# Distance-Alarm.net
KiCad netlist of a schematic drawn in EAGLE
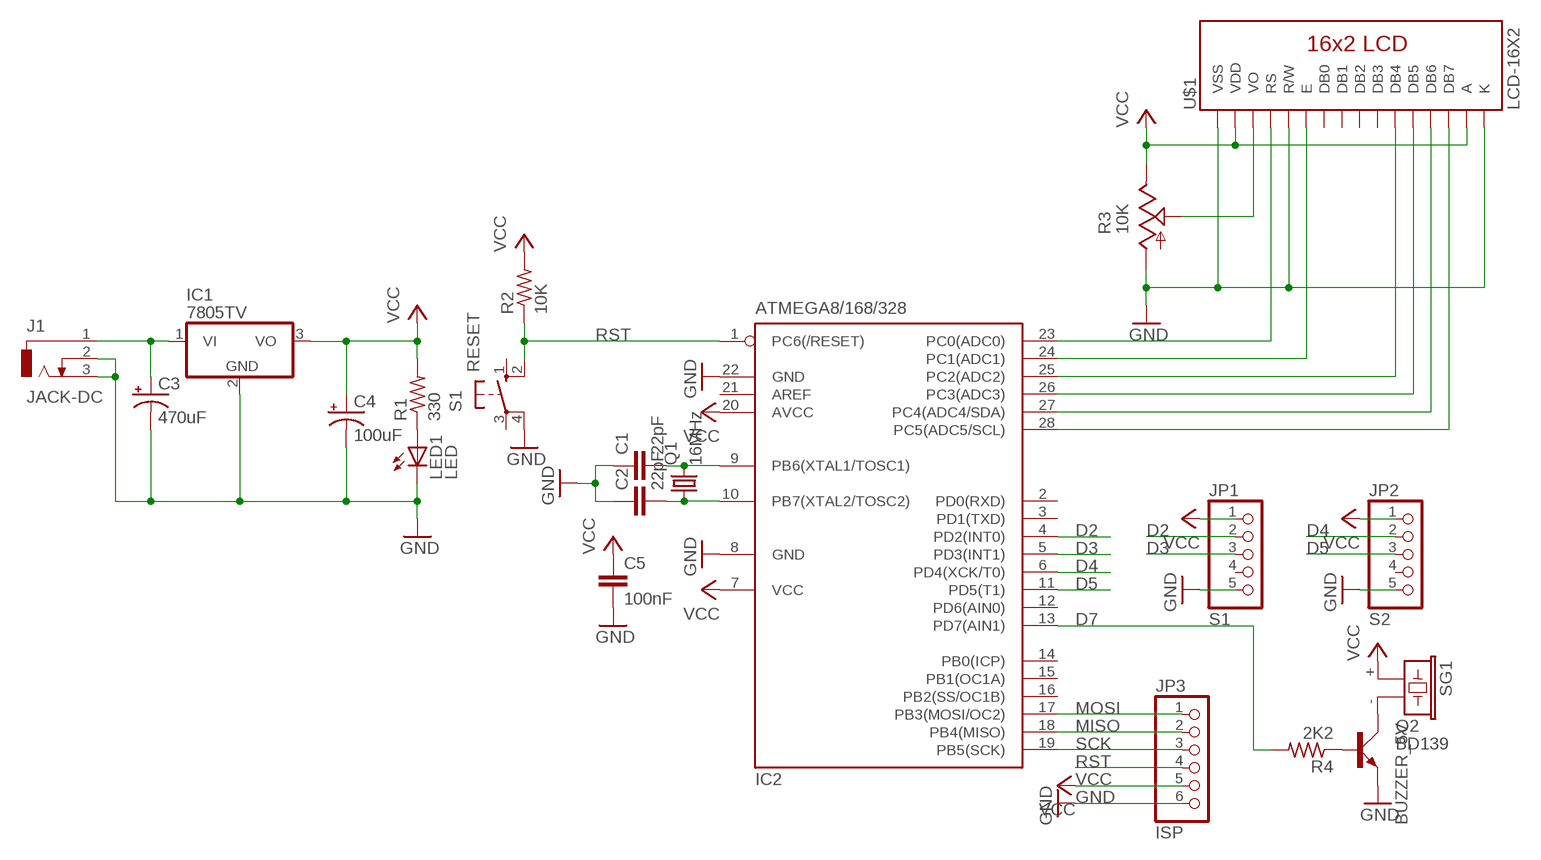
[diagram p0: schematic, sheet 1]

(export (version "E")
  (design (tool "Eeschema 10.0.6"))
  (components
    (comp (ref "C1")
      (value "22pF")
      (footprint "eagle-import:C025-024X044")
      (libsource (lib "eagle-import") (part "CAPACITOR-NONPOLAR025-024X044"))
    )
    (comp (ref "C2")
      (value "22pF")
      (footprint "eagle-import:C025-024X044")
      (libsource (lib "eagle-import") (part "CAPACITOR-NONPOLAR025-024X044"))
    )
    (comp (ref "C3")
      (value "470uF")
      (footprint "eagle-import:E2,5-6")
      (libsource (lib "eagle-import") (part "CAPACITOR-POLARE2.5-6"))
    )
    (comp (ref "C4")
      (value "100uF")
      (footprint "eagle-import:E2,5-6")
      (libsource (lib "eagle-import") (part "CAPACITOR-POLARE2.5-6"))
    )
    (comp (ref "C5")
      (value "100nF")
      (footprint "eagle-import:C025-024X044")
      (libsource (lib "eagle-import") (part "CAPACITOR-NONPOLAR025-024X044"))
    )
    (comp (ref "IC1")
      (value "7805TV")
      (footprint "eagle-import:TO220V")
      (libsource (lib "eagle-import") (part "78TV05"))
    )
    (comp (ref "IC2")
      (value "ATMEGA8/168/328")
      (footprint "eagle-import:DIL28-3")
      (libsource (lib "eagle-import") (part "ATMEGA8/168/328"))
    )
    (comp (ref "J1")
      (value "JACK-DC")
      (footprint "eagle-import:DCJ0202")
      (libsource (lib "eagle-import") (part "JACK-DC"))
    )
    (comp (ref "JP1")
      (value "S1")
      (footprint "eagle-import:1X05")
      (libsource (lib "eagle-import") (part "PINHD-1X5"))
    )
    (comp (ref "JP2")
      (value "S2")
      (footprint "eagle-import:1X05")
      (libsource (lib "eagle-import") (part "PINHD-1X5"))
    )
    (comp (ref "JP3")
      (value "ISP")
      (footprint "eagle-import:1X06")
      (libsource (lib "eagle-import") (part "PINHD-1X6"))
    )
    (comp (ref "LED1")
      (value "LED")
      (footprint "eagle-import:LED3MM")
      (libsource (lib "eagle-import") (part "LED3MM"))
    )
    (comp (ref "Q1")
      (value "16MHz")
      (footprint "eagle-import:HC49_S")
      (libsource (lib "eagle-import") (part "CRYSTALHC49S"))
    )
    (comp (ref "Q2")
      (value "BD139")
      (footprint "eagle-import:TO126AV")
      (libsource (lib "eagle-import") (part "BD139"))
    )
    (comp (ref "R1")
      (value "330")
      (footprint "eagle-import:0207_10")
      (libsource (lib "eagle-import") (part "RESISTOR0207/10"))
    )
    (comp (ref "R2")
      (value "10K")
      (footprint "eagle-import:0207_10")
      (libsource (lib "eagle-import") (part "RESISTOR0207/10"))
    )
    (comp (ref "R3")
      (value "10K")
      (footprint "eagle-import:CA6V")
      (libsource (lib "eagle-import") (part "TRIMPOTCA6V"))
    )
    (comp (ref "R4")
      (value "2K2")
      (footprint "eagle-import:0207_10")
      (libsource (lib "eagle-import") (part "RESISTOR0207/10"))
    )
    (comp (ref "S1")
      (value "RESET")
      (footprint "eagle-import:B3F-10XX")
      (fields (field (name "MPN") "B3F-1000"))
      (libsource (lib "eagle-import") (part "SW-PUSHBUTTON"))
    )
    (comp (ref "SG1")
      (value "BUZZER_5V")
      (footprint "eagle-import:BUZZER_F_CM12P")
      (libsource (lib "eagle-import") (part "BUZZER_5V"))
    )
    (comp (ref "U$1")
      (value "LCD-16X2")
      (footprint "eagle-import:LCD-16X2")
      (libsource (lib "eagle-import") (part "LCD-16X2"))
    )
  )
  (nets
    (net (code "1") (name "/D2") (class "Default")
      (node (ref "IC2") (pin "4") (pinfunction "PD2(INT0)_4") (pintype "bidirectional"))
      (node (ref "JP1") (pin "2") (pinfunction "2_2") (pintype "passive"))
    )
    (net (code "2") (name "/D3") (class "Default")
      (node (ref "IC2") (pin "5") (pinfunction "PD3(INT1)_5") (pintype "bidirectional"))
      (node (ref "JP1") (pin "3") (pinfunction "3_3") (pintype "passive"))
    )
    (net (code "3") (name "/D4") (class "Default")
      (node (ref "IC2") (pin "6") (pinfunction "PD4(XCK/T0)_6") (pintype "bidirectional"))
      (node (ref "JP2") (pin "2") (pinfunction "2_2") (pintype "passive"))
    )
    (net (code "4") (name "/D5") (class "Default")
      (node (ref "IC2") (pin "11") (pinfunction "PD5(T1)_11") (pintype "bidirectional"))
      (node (ref "JP2") (pin "3") (pinfunction "3_3") (pintype "passive"))
    )
    (net (code "5") (name "/D7") (class "Default")
      (node (ref "IC2") (pin "13") (pinfunction "PD7(AIN1)_13") (pintype "bidirectional"))
      (node (ref "R4") (pin "2") (pinfunction "2_2") (pintype "passive"))
    )
    (net (code "6") (name "/MISO") (class "Default")
      (node (ref "IC2") (pin "18") (pinfunction "PB4(MISO)_18") (pintype "bidirectional"))
      (node (ref "JP3") (pin "2") (pinfunction "2_2") (pintype "passive"))
    )
    (net (code "7") (name "/MOSI") (class "Default")
      (node (ref "IC2") (pin "17") (pinfunction "PB3(MOSI/OC2)_17") (pintype "bidirectional"))
      (node (ref "JP3") (pin "1") (pinfunction "1_1") (pintype "passive"))
    )
    (net (code "8") (name "/RST") (class "Default")
      (node (ref "IC2") (pin "1") (pinfunction "PC6(/RESET)_1") (pintype "bidirectional"))
      (node (ref "JP3") (pin "4") (pinfunction "4_4") (pintype "passive"))
      (node (ref "R2") (pin "1") (pinfunction "1_1") (pintype "passive"))
      (node (ref "S1") (pin "2") (pinfunction "S1_2") (pintype "passive"))
    )
    (net (code "9") (name "/SCK") (class "Default")
      (node (ref "IC2") (pin "19") (pinfunction "PB5(SCK)_19") (pintype "bidirectional"))
      (node (ref "JP3") (pin "3") (pinfunction "3_3") (pintype "passive"))
    )
    (net (code "10") (name "GND") (class "Default")
      (node (ref "C1") (pin "1") (pinfunction "1_1") (pintype "passive"))
      (node (ref "C2") (pin "1") (pinfunction "1_1") (pintype "passive"))
      (node (ref "C3") (pin "-") (pinfunction "-_-") (pintype "passive"))
      (node (ref "C4") (pin "-") (pinfunction "-_-") (pintype "passive"))
      (node (ref "C5") (pin "2") (pinfunction "2_2") (pintype "passive"))
      (node (ref "IC1") (pin "2") (pinfunction "GND_2") (pintype "passive"))
      (node (ref "IC2") (pin "22") (pinfunction "GND_22") (pintype "power_in"))
      (node (ref "IC2") (pin "8") (pinfunction "GND_8") (pintype "power_in"))
      (node (ref "J1") (pin "2") (pinfunction "2_2") (pintype "passive"))
      (node (ref "J1") (pin "3") (pinfunction "3_3") (pintype "passive"))
      (node (ref "JP1") (pin "5") (pinfunction "5_5") (pintype "passive"))
      (node (ref "JP2") (pin "5") (pinfunction "5_5") (pintype "passive"))
      (node (ref "JP3") (pin "6") (pinfunction "6_6") (pintype "passive"))
      (node (ref "LED1") (pin "K") (pinfunction "C_K") (pintype "passive"))
      (node (ref "Q2") (pin "E") (pinfunction "E_E") (pintype "passive"))
      (node (ref "R3") (pin "A") (pinfunction "A_A") (pintype "passive"))
      (node (ref "S1") (pin "4") (pinfunction "P1_4") (pintype "passive"))
      (node (ref "U$1") (pin "1") (pinfunction "VSS_1") (pintype "power_in"))
      (node (ref "U$1") (pin "16") (pinfunction "K_16") (pintype "power_in"))
      (node (ref "U$1") (pin "5") (pinfunction "R/W_5") (pintype "input"))
    )
    (net (code "11") (name "Net-(IC1-VI)") (class "Default")
      (node (ref "C3") (pin "+") (pinfunction "+_+") (pintype "passive"))
      (node (ref "IC1") (pin "1") (pinfunction "VI_1") (pintype "input"))
      (node (ref "J1") (pin "1") (pinfunction "1_1") (pintype "passive"))
    )
    (net (code "12") (name "Net-(IC2-PB6(XTAL1{slash}TOSC1))") (class "Default")
      (node (ref "C1") (pin "2") (pinfunction "2_2") (pintype "passive"))
      (node (ref "IC2") (pin "9") (pinfunction "PB6(XTAL1/TOSC1)_9") (pintype "bidirectional"))
      (node (ref "Q1") (pin "2") (pinfunction "2_2") (pintype "passive"))
    )
    (net (code "13") (name "Net-(IC2-PB7(XTAL2{slash}TOSC2))") (class "Default")
      (node (ref "C2") (pin "2") (pinfunction "2_2") (pintype "passive"))
      (node (ref "IC2") (pin "10") (pinfunction "PB7(XTAL2/TOSC2)_10") (pintype "bidirectional"))
      (node (ref "Q1") (pin "1") (pinfunction "1_1") (pintype "passive"))
    )
    (net (code "14") (name "Net-(IC2-PC0(ADC0))") (class "Default")
      (node (ref "IC2") (pin "23") (pinfunction "PC0(ADC0)_23") (pintype "bidirectional"))
      (node (ref "U$1") (pin "4") (pinfunction "RS_4") (pintype "input"))
    )
    (net (code "15") (name "Net-(IC2-PC1(ADC1))") (class "Default")
      (node (ref "IC2") (pin "24") (pinfunction "PC1(ADC1)_24") (pintype "bidirectional"))
      (node (ref "U$1") (pin "6") (pinfunction "E_6") (pintype "input"))
    )
    (net (code "16") (name "Net-(IC2-PC2(ADC2))") (class "Default")
      (node (ref "IC2") (pin "25") (pinfunction "PC2(ADC2)_25") (pintype "bidirectional"))
      (node (ref "U$1") (pin "11") (pinfunction "DB4_11") (pintype "bidirectional"))
    )
    (net (code "17") (name "Net-(IC2-PC3(ADC3))") (class "Default")
      (node (ref "IC2") (pin "26") (pinfunction "PC3(ADC3)_26") (pintype "bidirectional"))
      (node (ref "U$1") (pin "12") (pinfunction "DB5_12") (pintype "bidirectional"))
    )
    (net (code "18") (name "Net-(IC2-PC4(ADC4{slash}SDA))") (class "Default")
      (node (ref "IC2") (pin "27") (pinfunction "PC4(ADC4/SDA)_27") (pintype "bidirectional"))
      (node (ref "U$1") (pin "13") (pinfunction "DB6_13") (pintype "bidirectional"))
    )
    (net (code "19") (name "Net-(IC2-PC5(ADC5{slash}SCL))") (class "Default")
      (node (ref "IC2") (pin "28") (pinfunction "PC5(ADC5/SCL)_28") (pintype "bidirectional"))
      (node (ref "U$1") (pin "14") (pinfunction "DB7_14") (pintype "bidirectional"))
    )
    (net (code "20") (name "Net-(LED1-PadA)") (class "Default")
      (node (ref "LED1") (pin "A") (pinfunction "A_A") (pintype "passive"))
      (node (ref "R1") (pin "1") (pinfunction "1_1") (pintype "passive"))
    )
    (net (code "21") (name "Net-(Q2-PadB)") (class "Default")
      (node (ref "Q2") (pin "B") (pinfunction "B_B") (pintype "passive"))
      (node (ref "R4") (pin "1") (pinfunction "1_1") (pintype "passive"))
    )
    (net (code "22") (name "Net-(SG1-2)") (class "Default")
      (node (ref "Q2") (pin "C") (pinfunction "C_C") (pintype "passive"))
      (node (ref "SG1") (pin "-") (pinfunction "2_-") (pintype "passive"))
    )
    (net (code "23") (name "Net-(U$1-VO)") (class "Default")
      (node (ref "R3") (pin "S") (pinfunction "S_S") (pintype "passive"))
      (node (ref "U$1") (pin "3") (pinfunction "VO_3") (pintype "bidirectional"))
    )
    (net (code "24") (name "VCC") (class "Default")
      (node (ref "C4") (pin "+") (pinfunction "+_+") (pintype "passive"))
      (node (ref "C5") (pin "1") (pinfunction "1_1") (pintype "passive"))
      (node (ref "IC1") (pin "3") (pinfunction "VO_3") (pintype "passive"))
      (node (ref "IC2") (pin "20") (pinfunction "AVCC_20") (pintype "power_in"))
      (node (ref "IC2") (pin "7") (pinfunction "VCC_7") (pintype "power_in"))
      (node (ref "JP1") (pin "1") (pinfunction "1_1") (pintype "passive"))
      (node (ref "JP2") (pin "1") (pinfunction "1_1") (pintype "passive"))
      (node (ref "JP3") (pin "5") (pinfunction "5_5") (pintype "passive"))
      (node (ref "R1") (pin "2") (pinfunction "2_2") (pintype "passive"))
      (node (ref "R2") (pin "2") (pinfunction "2_2") (pintype "passive"))
      (node (ref "R3") (pin "E") (pinfunction "E_E") (pintype "passive"))
      (node (ref "SG1") (pin "+") (pinfunction "1_+") (pintype "passive"))
      (node (ref "U$1") (pin "15") (pinfunction "A_15") (pintype "power_in"))
      (node (ref "U$1") (pin "2") (pinfunction "VDD_2") (pintype "power_in"))
    )
    (net (code "25") (name "unconnected-(IC2-AREF-Pad21)") (class "Default")
      (node (ref "IC2") (pin "21") (pinfunction "AREF_21") (pintype "passive"))
    )
    (net (code "26") (name "unconnected-(IC2-PB0(ICP)-Pad14)") (class "Default")
      (node (ref "IC2") (pin "14") (pinfunction "PB0(ICP)_14") (pintype "bidirectional"))
    )
    (net (code "27") (name "unconnected-(IC2-PB1(OC1A)-Pad15)") (class "Default")
      (node (ref "IC2") (pin "15") (pinfunction "PB1(OC1A)_15") (pintype "bidirectional"))
    )
    (net (code "28") (name "unconnected-(IC2-PB2(SS{slash}OC1B)-Pad16)") (class "Default")
      (node (ref "IC2") (pin "16") (pinfunction "PB2(SS/OC1B)_16") (pintype "bidirectional"))
    )
    (net (code "29") (name "unconnected-(IC2-PD0(RXD)-Pad2)") (class "Default")
      (node (ref "IC2") (pin "2") (pinfunction "PD0(RXD)_2") (pintype "bidirectional"))
    )
    (net (code "30") (name "unconnected-(IC2-PD1(TXD)-Pad3)") (class "Default")
      (node (ref "IC2") (pin "3") (pinfunction "PD1(TXD)_3") (pintype "bidirectional"))
    )
    (net (code "31") (name "unconnected-(IC2-PD6(AIN0)-Pad12)") (class "Default")
      (node (ref "IC2") (pin "12") (pinfunction "PD6(AIN0)_12") (pintype "bidirectional"))
    )
    (net (code "32") (name "unconnected-(JP1-Pad4)") (class "Default")
      (node (ref "JP1") (pin "4") (pinfunction "4_4") (pintype "passive"))
    )
    (net (code "33") (name "unconnected-(JP2-Pad4)") (class "Default")
      (node (ref "JP2") (pin "4") (pinfunction "4_4") (pintype "passive"))
    )
    (net (code "34") (name "unconnected-(S1-P-Pad3)") (class "Default")
      (node (ref "S1") (pin "3") (pinfunction "P_3") (pintype "passive"))
    )
    (net (code "35") (name "unconnected-(S1-S-Pad1)") (class "Default")
      (node (ref "S1") (pin "1") (pinfunction "S_1") (pintype "passive"))
    )
    (net (code "36") (name "unconnected-(U$1-DB0-Pad7)") (class "Default")
      (node (ref "U$1") (pin "7") (pinfunction "DB0_7") (pintype "bidirectional"))
    )
    (net (code "37") (name "unconnected-(U$1-DB1-Pad8)") (class "Default")
      (node (ref "U$1") (pin "8") (pinfunction "DB1_8") (pintype "bidirectional"))
    )
    (net (code "38") (name "unconnected-(U$1-DB2-Pad9)") (class "Default")
      (node (ref "U$1") (pin "9") (pinfunction "DB2_9") (pintype "bidirectional"))
    )
    (net (code "39") (name "unconnected-(U$1-DB3-Pad10)") (class "Default")
      (node (ref "U$1") (pin "10") (pinfunction "DB3_10") (pintype "bidirectional"))
    )
  )
)
